# SimulatorT2SecondPCRevB.net
KiCad netlist of a schematic drawn in EAGLE
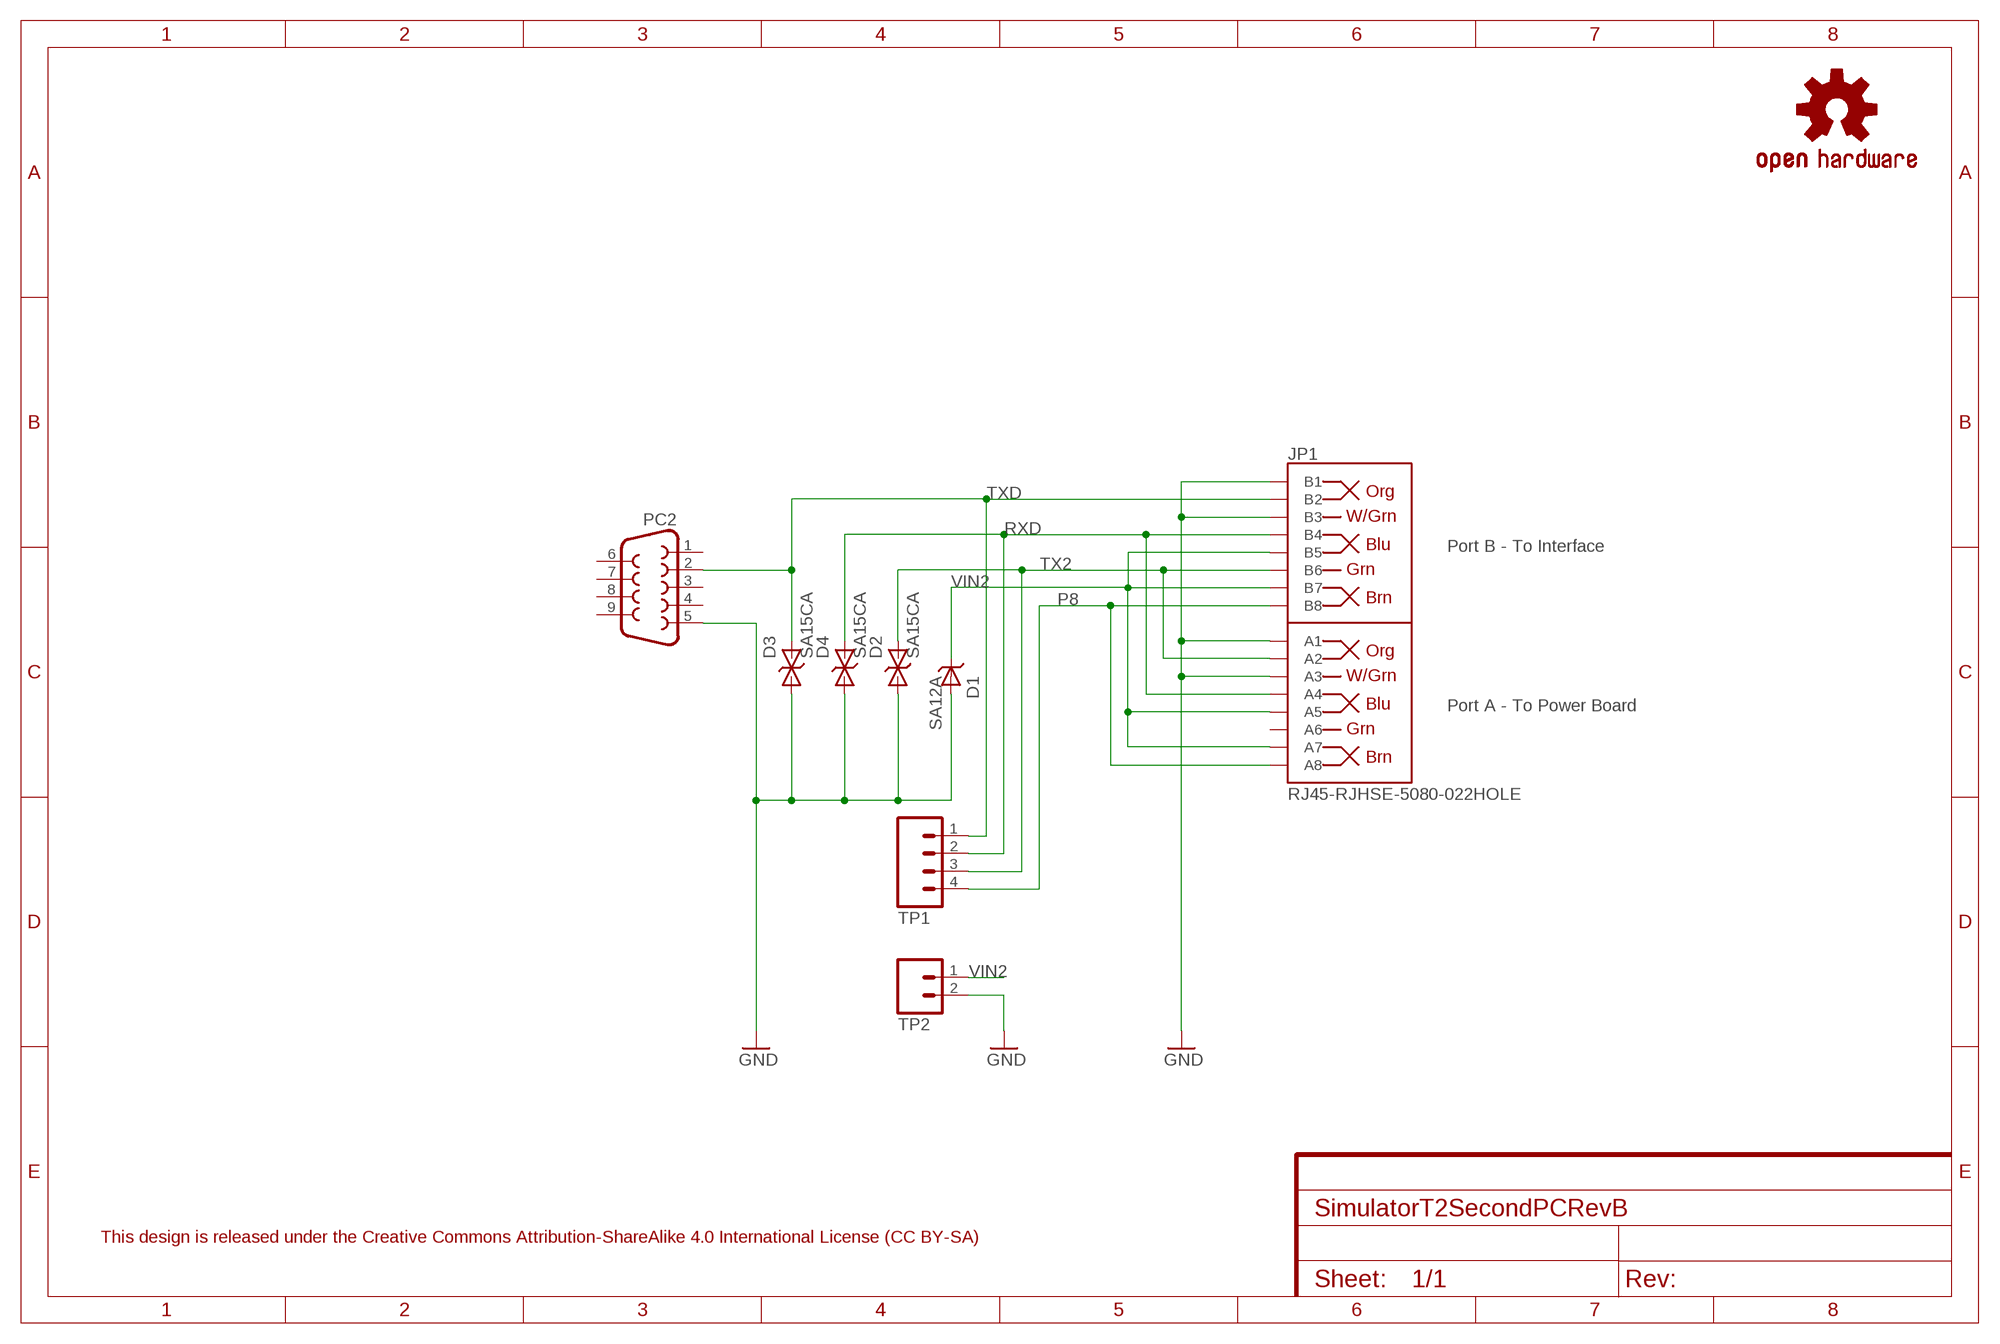
[diagram p0: schematic, sheet 1]

(export (version "E")
  (design (tool "Eeschema 10.0.6"))
  (components
    (comp (ref "D1")
      (value "SA12A")
      (footprint "eagle-import:DO41_TVS_UNI")
      (libsource (lib "eagle-import") (part "SA12A"))
    )
    (comp (ref "D2")
      (value "SA15CA")
      (footprint "eagle-import:DO41_TVS_BI")
      (libsource (lib "eagle-import") (part "SA15CA"))
    )
    (comp (ref "D3")
      (value "SA15CA")
      (footprint "eagle-import:DO41_TVS_BI")
      (libsource (lib "eagle-import") (part "SA15CA"))
    )
    (comp (ref "D4")
      (value "SA15CA")
      (footprint "eagle-import:DO41_TVS_BI")
      (libsource (lib "eagle-import") (part "SA15CA"))
    )
    (comp (ref "JP1")
      (value "RJ45-RJHSE-5080-022HOLE")
      (footprint "eagle-import:RJ45-RJHSE-5080-02")
      (libsource (lib "eagle-import") (part "RJ45-RJHSE-5080-022HOLE"))
    )
    (comp (ref "LOGO1")
      (value "OSHW-LOGOS")
      (footprint "eagle-import:OSHW-LOGO-S")
      (libsource (lib "eagle-import") (part "OSHW-LOGOS"))
    )
    (comp (ref "PC2")
      (value "DB9-CONNECTOR-PCBFEMALE")
      (footprint "eagle-import:MULTICOMP-DB9-FEMALE-PCB-90DEG")
      (libsource (lib "eagle-import") (part "DB9-CONNECTOR-PCBFEMALE"))
    )
    (comp (ref "TP1")
      (value "M04PTH")
      (footprint "eagle-import:1X04")
      (libsource (lib "eagle-import") (part "M04PTH"))
    )
    (comp (ref "TP2")
      (value "M02PTH")
      (footprint "eagle-import:1X02")
      (libsource (lib "eagle-import") (part "M02PTH"))
    )
  )
  (nets
    (net (code "1") (name "/P8") (class "Default")
      (node (ref "JP1") (pin "A8") (pinfunction "A8_A8") (pintype "bidirectional"))
      (node (ref "JP1") (pin "B8") (pinfunction "B8_B8") (pintype "bidirectional"))
      (node (ref "TP1") (pin "4") (pinfunction "4_4") (pintype "passive"))
    )
    (net (code "2") (name "/RXD") (class "Default")
      (node (ref "D4") (pin "C") (pinfunction "C_C") (pintype "passive"))
      (node (ref "JP1") (pin "A4") (pinfunction "A4_A4") (pintype "bidirectional"))
      (node (ref "JP1") (pin "B4") (pinfunction "B4_B4") (pintype "bidirectional"))
      (node (ref "TP1") (pin "2") (pinfunction "2_2") (pintype "passive"))
    )
    (net (code "3") (name "/TX2") (class "Default")
      (node (ref "D2") (pin "C") (pinfunction "C_C") (pintype "passive"))
      (node (ref "JP1") (pin "A2") (pinfunction "A2_A2") (pintype "bidirectional"))
      (node (ref "JP1") (pin "B6") (pinfunction "B6_B6") (pintype "bidirectional"))
      (node (ref "TP1") (pin "3") (pinfunction "3_3") (pintype "passive"))
    )
    (net (code "4") (name "/TXD") (class "Default")
      (node (ref "D3") (pin "C") (pinfunction "C_C") (pintype "passive"))
      (node (ref "JP1") (pin "B2") (pinfunction "B2_B2") (pintype "bidirectional"))
      (node (ref "PC2") (pin "2") (pinfunction "2_2") (pintype "passive"))
      (node (ref "TP1") (pin "1") (pinfunction "1_1") (pintype "passive"))
    )
    (net (code "5") (name "/VIN2") (class "Default")
      (node (ref "D1") (pin "CATHODE") (pinfunction "CATHODE_CATHODE") (pintype "passive"))
      (node (ref "JP1") (pin "A5") (pinfunction "A5_A5") (pintype "bidirectional"))
      (node (ref "JP1") (pin "A7") (pinfunction "A7_A7") (pintype "bidirectional"))
      (node (ref "JP1") (pin "B5") (pinfunction "B5_B5") (pintype "bidirectional"))
      (node (ref "JP1") (pin "B7") (pinfunction "B7_B7") (pintype "bidirectional"))
      (node (ref "TP2") (pin "1") (pinfunction "1_1") (pintype "passive"))
    )
    (net (code "6") (name "GND") (class "Default")
      (node (ref "D1") (pin "ANODE") (pinfunction "ANODE_ANODE") (pintype "passive"))
      (node (ref "D2") (pin "A") (pinfunction "A_A") (pintype "passive"))
      (node (ref "D3") (pin "A") (pinfunction "A_A") (pintype "passive"))
      (node (ref "D4") (pin "A") (pinfunction "A_A") (pintype "passive"))
      (node (ref "JP1") (pin "A1") (pinfunction "A1_A1") (pintype "bidirectional"))
      (node (ref "JP1") (pin "A3") (pinfunction "A3_A3") (pintype "bidirectional"))
      (node (ref "JP1") (pin "B1") (pinfunction "B1_B1") (pintype "bidirectional"))
      (node (ref "JP1") (pin "B3") (pinfunction "B3_B3") (pintype "bidirectional"))
      (node (ref "PC2") (pin "5") (pinfunction "5_5") (pintype "passive"))
      (node (ref "TP2") (pin "2") (pinfunction "2_2") (pintype "passive"))
    )
    (net (code "7") (name "unconnected-(JP1-PadA6)") (class "Default")
      (node (ref "JP1") (pin "A6") (pinfunction "A6_A6") (pintype "bidirectional"))
    )
    (net (code "8") (name "unconnected-(PC2-Pad1)") (class "Default")
      (node (ref "PC2") (pin "1") (pinfunction "1_1") (pintype "passive"))
    )
    (net (code "9") (name "unconnected-(PC2-Pad3)") (class "Default")
      (node (ref "PC2") (pin "3") (pinfunction "3_3") (pintype "passive"))
    )
    (net (code "10") (name "unconnected-(PC2-Pad4)") (class "Default")
      (node (ref "PC2") (pin "4") (pinfunction "4_4") (pintype "passive"))
    )
    (net (code "11") (name "unconnected-(PC2-Pad6)") (class "Default")
      (node (ref "PC2") (pin "6") (pinfunction "6_6") (pintype "passive"))
    )
    (net (code "12") (name "unconnected-(PC2-Pad7)") (class "Default")
      (node (ref "PC2") (pin "7") (pinfunction "7_7") (pintype "passive"))
    )
    (net (code "13") (name "unconnected-(PC2-Pad8)") (class "Default")
      (node (ref "PC2") (pin "8") (pinfunction "8_8") (pintype "passive"))
    )
    (net (code "14") (name "unconnected-(PC2-Pad9)") (class "Default")
      (node (ref "PC2") (pin "9") (pinfunction "9_9") (pintype "passive"))
    )
  )
)
